# TapuinoMini.net
KiCad netlist of a schematic drawn in EAGLE
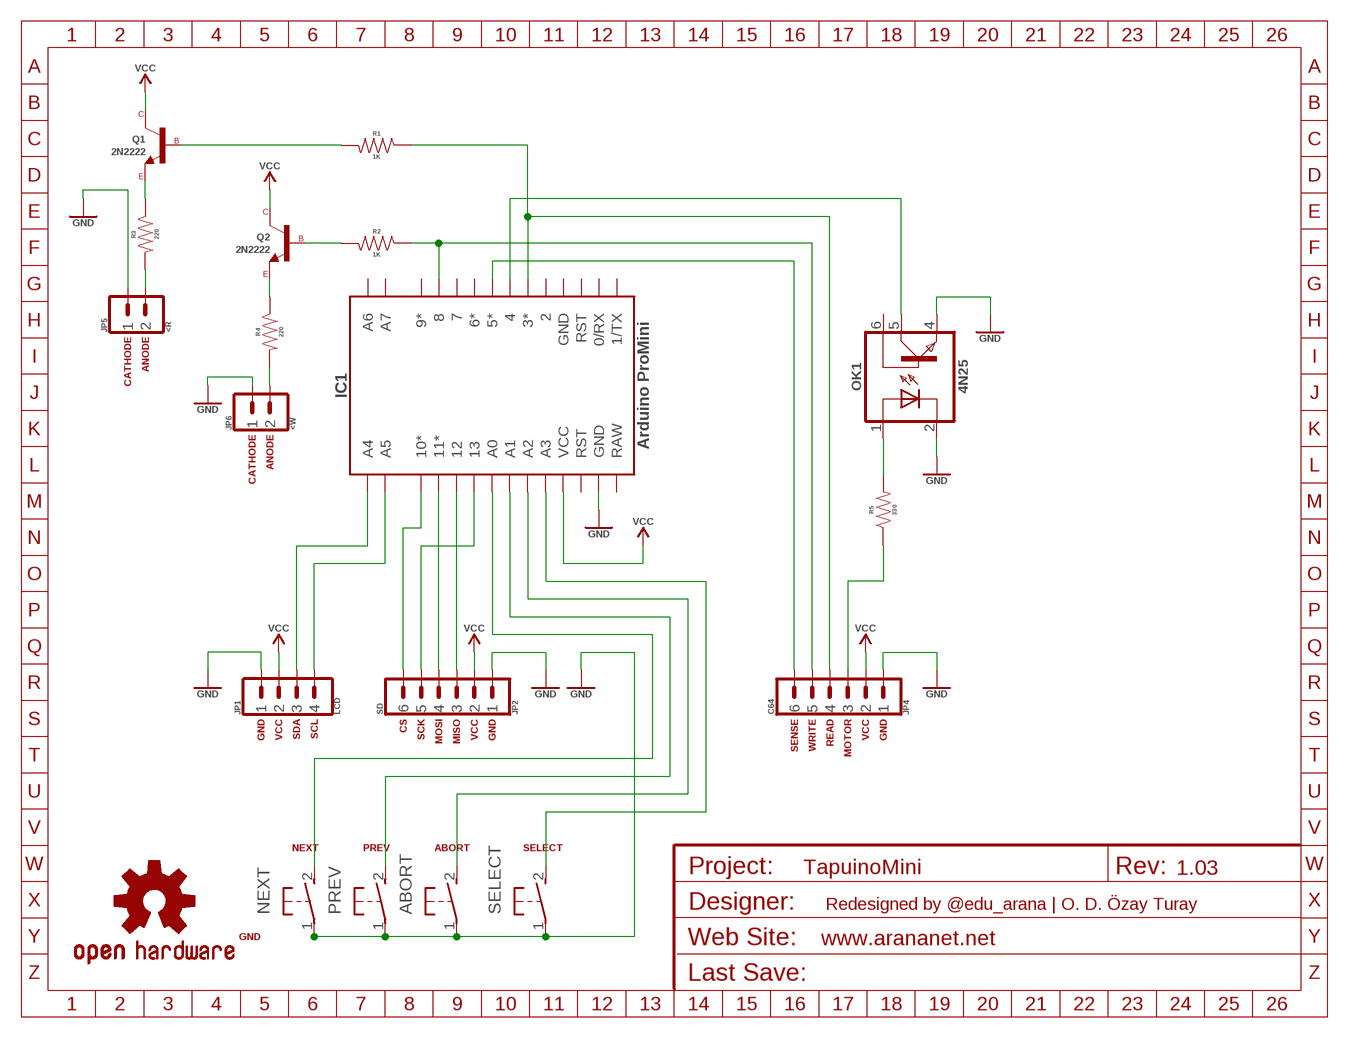
[diagram p0: schematic, sheet 1]

(export (version "E")
  (design (tool "Eeschema 10.0.6"))
  (components
    (comp (ref "ABORT")
      (value "31-XX")
      (footprint "eagle-import:B3F-31XX")
      (fields (field (name "MPN") "B3F-3100"))
      (libsource (lib "eagle-import") (part "31-XX"))
    )
    (comp (ref "IC1")
      (value "Arduino ProMini")
      (footprint "eagle-import:PROMINI_A")
      (libsource (lib "eagle-import") (part "PROMINI_A"))
    )
    (comp (ref "JP1")
      (value "LCD")
      (footprint "eagle-import:1X04_SQR")
      (libsource (lib "eagle-import") (part "1X04_SQR"))
    )
    (comp (ref "JP2")
      (value "SD")
      (footprint "eagle-import:1X06_SQR")
      (libsource (lib "eagle-import") (part "1X06_SQR"))
    )
    (comp (ref "JP4")
      (value "C64")
      (footprint "eagle-import:1X06_SQR")
      (libsource (lib "eagle-import") (part "1X06_SQR"))
    )
    (comp (ref "JP5")
      (value "<R")
      (footprint "eagle-import:1X02_SQR")
      (libsource (lib "eagle-import") (part "1X02_SQR"))
    )
    (comp (ref "JP6")
      (value "<W")
      (footprint "eagle-import:1X02_SQR")
      (libsource (lib "eagle-import") (part "1X02_SQR"))
    )
    (comp (ref "LOGO1")
      (value "OSHW-LOGOL")
      (footprint "eagle-import:OSHW-LOGO-L")
      (libsource (lib "eagle-import") (part "OSHW-LOGOL"))
    )
    (comp (ref "NEXT")
      (value "31-XX")
      (footprint "eagle-import:B3F-31XX")
      (fields (field (name "MPN") "B3F-3100"))
      (libsource (lib "eagle-import") (part "31-XX"))
    )
    (comp (ref "OK1")
      (value "4N25")
      (footprint "eagle-import:DIP06")
      (libsource (lib "eagle-import") (part "OPTO_6PIN_4NXX"))
    )
    (comp (ref "PREV")
      (value "31-XX")
      (footprint "eagle-import:B3F-31XX")
      (fields (field (name "MPN") "B3F-3100"))
      (libsource (lib "eagle-import") (part "31-XX"))
    )
    (comp (ref "Q1")
      (value "2N2222")
      (footprint "eagle-import:TO-92")
      (libsource (lib "eagle-import") (part "TRANSISTOR_NPN_EBC"))
    )
    (comp (ref "Q2")
      (value "2N2222")
      (footprint "eagle-import:TO-92")
      (libsource (lib "eagle-import") (part "TRANSISTOR_NPN_EBC"))
    )
    (comp (ref "R1")
      (value "1K")
      (footprint "eagle-import:RESISTOR_PTH_0.3")
      (libsource (lib "eagle-import") (part "RESISTOR_PTH_0.3"))
    )
    (comp (ref "R2")
      (value "1K")
      (footprint "eagle-import:RESISTOR_PTH_0.3")
      (libsource (lib "eagle-import") (part "RESISTOR_PTH_0.3"))
    )
    (comp (ref "R3")
      (value "220")
      (footprint "eagle-import:RESISTOR_PTH_0.3")
      (libsource (lib "eagle-import") (part "RESISTOR_PTH_0.3"))
    )
    (comp (ref "R4")
      (value "220")
      (footprint "eagle-import:RESISTOR_PTH_0.3")
      (libsource (lib "eagle-import") (part "RESISTOR_PTH_0.3"))
    )
    (comp (ref "R5")
      (value "330")
      (footprint "eagle-import:RESISTOR_PTH_0.3")
      (libsource (lib "eagle-import") (part "RESISTOR_PTH_0.3"))
    )
    (comp (ref "SELECT")
      (value "31-XX")
      (footprint "eagle-import:B3F-31XX")
      (fields (field (name "MPN") "B3F-3100"))
      (libsource (lib "eagle-import") (part "31-XX"))
    )
  )
  (nets
    (net (code "1") (name "GND") (class "Default")
      (node (ref "ABORT") (pin "1") (pinfunction "P_1") (pintype "passive"))
      (node (ref "IC1") (pin "GND@1") (pinfunction "GND_GND@1") (pintype "bidirectional"))
      (node (ref "JP1") (pin "1") (pinfunction "1_1") (pintype "passive"))
      (node (ref "JP2") (pin "1") (pinfunction "1_1") (pintype "passive"))
      (node (ref "JP4") (pin "1") (pinfunction "1_1") (pintype "passive"))
      (node (ref "JP5") (pin "1") (pinfunction "1_1") (pintype "passive"))
      (node (ref "JP6") (pin "1") (pinfunction "1_1") (pintype "passive"))
      (node (ref "NEXT") (pin "1") (pinfunction "P_1") (pintype "passive"))
      (node (ref "OK1") (pin "2") (pinfunction "CATHODE_2") (pintype "passive"))
      (node (ref "OK1") (pin "4") (pinfunction "EMITTER_4") (pintype "passive"))
      (node (ref "PREV") (pin "1") (pinfunction "P_1") (pintype "passive"))
      (node (ref "SELECT") (pin "1") (pinfunction "P_1") (pintype "passive"))
    )
    (net (code "2") (name "Net-(ABORT-S)") (class "Default")
      (node (ref "ABORT") (pin "2") (pinfunction "S_2") (pintype "passive"))
      (node (ref "IC1") (pin "A2") (pinfunction "A2_A2") (pintype "bidirectional"))
    )
    (net (code "3") (name "Net-(IC1-Pad3*)") (class "Default")
      (node (ref "IC1") (pin "3*") (pinfunction "3*_3*") (pintype "bidirectional"))
      (node (ref "JP4") (pin "4") (pinfunction "4_4") (pintype "passive"))
      (node (ref "R1") (pin "1") (pinfunction "1_1") (pintype "passive"))
    )
    (net (code "4") (name "Net-(IC1-Pad5*)") (class "Default")
      (node (ref "IC1") (pin "5*") (pinfunction "5*_5*") (pintype "bidirectional"))
      (node (ref "JP4") (pin "6") (pinfunction "6_6") (pintype "passive"))
    )
    (net (code "5") (name "Net-(IC1-Pad8)") (class "Default")
      (node (ref "IC1") (pin "8") (pinfunction "8_8") (pintype "bidirectional"))
      (node (ref "JP4") (pin "5") (pinfunction "5_5") (pintype "passive"))
      (node (ref "R2") (pin "1") (pinfunction "1_1") (pintype "passive"))
    )
    (net (code "6") (name "Net-(IC1-Pad10*)") (class "Default")
      (node (ref "IC1") (pin "10*") (pinfunction "10*_10*") (pintype "bidirectional"))
      (node (ref "JP2") (pin "6") (pinfunction "6_6") (pintype "passive"))
    )
    (net (code "7") (name "Net-(IC1-Pad11*)") (class "Default")
      (node (ref "IC1") (pin "11*") (pinfunction "11*_11*") (pintype "bidirectional"))
      (node (ref "JP2") (pin "4") (pinfunction "4_4") (pintype "passive"))
    )
    (net (code "8") (name "Net-(IC1-Pad12)") (class "Default")
      (node (ref "IC1") (pin "12") (pinfunction "12_12") (pintype "bidirectional"))
      (node (ref "JP2") (pin "3") (pinfunction "3_3") (pintype "passive"))
    )
    (net (code "9") (name "Net-(IC1-Pad13)") (class "Default")
      (node (ref "IC1") (pin "13") (pinfunction "13_13") (pintype "bidirectional"))
      (node (ref "JP2") (pin "5") (pinfunction "5_5") (pintype "passive"))
    )
    (net (code "10") (name "Net-(IC1-PadA4)") (class "Default")
      (node (ref "IC1") (pin "A4") (pinfunction "A4_A4") (pintype "bidirectional"))
      (node (ref "JP1") (pin "3") (pinfunction "3_3") (pintype "passive"))
    )
    (net (code "11") (name "Net-(IC1-PadA5)") (class "Default")
      (node (ref "IC1") (pin "A5") (pinfunction "A5_A5") (pintype "bidirectional"))
      (node (ref "JP1") (pin "4") (pinfunction "4_4") (pintype "passive"))
    )
    (net (code "12") (name "Net-(JP4-Pad3)") (class "Default")
      (node (ref "JP4") (pin "3") (pinfunction "3_3") (pintype "passive"))
      (node (ref "R5") (pin "1") (pinfunction "1_1") (pintype "passive"))
    )
    (net (code "13") (name "Net-(JP5-Pad2)") (class "Default")
      (node (ref "JP5") (pin "2") (pinfunction "2_2") (pintype "passive"))
      (node (ref "R3") (pin "2") (pinfunction "2_2") (pintype "passive"))
    )
    (net (code "14") (name "Net-(JP6-Pad2)") (class "Default")
      (node (ref "JP6") (pin "2") (pinfunction "2_2") (pintype "passive"))
      (node (ref "R4") (pin "2") (pinfunction "2_2") (pintype "passive"))
    )
    (net (code "15") (name "Net-(NEXT-S)") (class "Default")
      (node (ref "IC1") (pin "A0") (pinfunction "A0_A0") (pintype "bidirectional"))
      (node (ref "NEXT") (pin "2") (pinfunction "S_2") (pintype "passive"))
    )
    (net (code "16") (name "Net-(OK1-ANODE)") (class "Default")
      (node (ref "OK1") (pin "1") (pinfunction "ANODE_1") (pintype "passive"))
      (node (ref "R5") (pin "2") (pinfunction "2_2") (pintype "passive"))
    )
    (net (code "17") (name "Net-(OK1-COLLECTOR)") (class "Default")
      (node (ref "IC1") (pin "4") (pinfunction "4_4") (pintype "bidirectional"))
      (node (ref "OK1") (pin "5") (pinfunction "COLLECTOR_5") (pintype "passive"))
    )
    (net (code "18") (name "Net-(PREV-S)") (class "Default")
      (node (ref "IC1") (pin "A1") (pinfunction "A1_A1") (pintype "bidirectional"))
      (node (ref "PREV") (pin "2") (pinfunction "S_2") (pintype "passive"))
    )
    (net (code "19") (name "Net-(Q1-BASE)") (class "Default")
      (node (ref "Q1") (pin "2") (pinfunction "BASE_2") (pintype "passive"))
      (node (ref "R1") (pin "2") (pinfunction "2_2") (pintype "passive"))
    )
    (net (code "20") (name "Net-(Q1-EMITTER)") (class "Default")
      (node (ref "Q1") (pin "1") (pinfunction "EMITTER_1") (pintype "passive"))
      (node (ref "R3") (pin "1") (pinfunction "1_1") (pintype "passive"))
    )
    (net (code "21") (name "Net-(Q2-BASE)") (class "Default")
      (node (ref "Q2") (pin "2") (pinfunction "BASE_2") (pintype "passive"))
      (node (ref "R2") (pin "2") (pinfunction "2_2") (pintype "passive"))
    )
    (net (code "22") (name "Net-(Q2-EMITTER)") (class "Default")
      (node (ref "Q2") (pin "1") (pinfunction "EMITTER_1") (pintype "passive"))
      (node (ref "R4") (pin "1") (pinfunction "1_1") (pintype "passive"))
    )
    (net (code "23") (name "Net-(SELECT-S)") (class "Default")
      (node (ref "IC1") (pin "A3") (pinfunction "A3_A3") (pintype "bidirectional"))
      (node (ref "SELECT") (pin "2") (pinfunction "S_2") (pintype "passive"))
    )
    (net (code "24") (name "VCC") (class "Default")
      (node (ref "IC1") (pin "VCC") (pinfunction "VCC_VCC") (pintype "bidirectional"))
      (node (ref "JP1") (pin "2") (pinfunction "2_2") (pintype "passive"))
      (node (ref "JP2") (pin "2") (pinfunction "2_2") (pintype "passive"))
      (node (ref "JP4") (pin "2") (pinfunction "2_2") (pintype "passive"))
      (node (ref "Q1") (pin "3") (pinfunction "COLLECTOR_3") (pintype "passive"))
      (node (ref "Q2") (pin "3") (pinfunction "COLLECTOR_3") (pintype "passive"))
    )
    (net (code "25") (name "unconnected-(IC1-GND-PadGND@2)") (class "Default")
      (node (ref "IC1") (pin "GND@2") (pinfunction "GND_GND@2") (pintype "bidirectional"))
    )
    (net (code "26") (name "unconnected-(IC1-Pad0{slash}RX)") (class "Default")
      (node (ref "IC1") (pin "0/RX") (pinfunction "0/RX_0/RX") (pintype "bidirectional"))
    )
    (net (code "27") (name "unconnected-(IC1-Pad1{slash}TX)") (class "Default")
      (node (ref "IC1") (pin "1/TX") (pinfunction "1/TX_1/TX") (pintype "bidirectional"))
    )
    (net (code "28") (name "unconnected-(IC1-Pad2)") (class "Default")
      (node (ref "IC1") (pin "2") (pinfunction "2_2") (pintype "bidirectional"))
    )
    (net (code "29") (name "unconnected-(IC1-Pad6*)") (class "Default")
      (node (ref "IC1") (pin "6*") (pinfunction "6*_6*") (pintype "bidirectional"))
    )
    (net (code "30") (name "unconnected-(IC1-Pad7)") (class "Default")
      (node (ref "IC1") (pin "7") (pinfunction "7_7") (pintype "bidirectional"))
    )
    (net (code "31") (name "unconnected-(IC1-Pad9*)") (class "Default")
      (node (ref "IC1") (pin "9*") (pinfunction "9*_9*") (pintype "bidirectional"))
    )
    (net (code "32") (name "unconnected-(IC1-PadA6)") (class "Default")
      (node (ref "IC1") (pin "A6") (pinfunction "A6_A6") (pintype "bidirectional"))
    )
    (net (code "33") (name "unconnected-(IC1-PadA7)") (class "Default")
      (node (ref "IC1") (pin "A7") (pinfunction "A7_A7") (pintype "bidirectional"))
    )
    (net (code "34") (name "unconnected-(IC1-PadRAW)") (class "Default")
      (node (ref "IC1") (pin "RAW") (pinfunction "RAW_RAW") (pintype "bidirectional"))
    )
    (net (code "35") (name "unconnected-(IC1-RST-PadRST@1)") (class "Default")
      (node (ref "IC1") (pin "RST@1") (pinfunction "RST_RST@1") (pintype "bidirectional"))
    )
    (net (code "36") (name "unconnected-(IC1-RST-PadRST@2)") (class "Default")
      (node (ref "IC1") (pin "RST@2") (pinfunction "RST_RST@2") (pintype "bidirectional"))
    )
    (net (code "37") (name "unconnected-(OK1-BASE-Pad6)") (class "Default")
      (node (ref "OK1") (pin "6") (pinfunction "BASE_6") (pintype "passive"))
    )
  )
)
